# hdmi_fpc_rev2.net
KiCad netlist of a schematic drawn in EAGLE
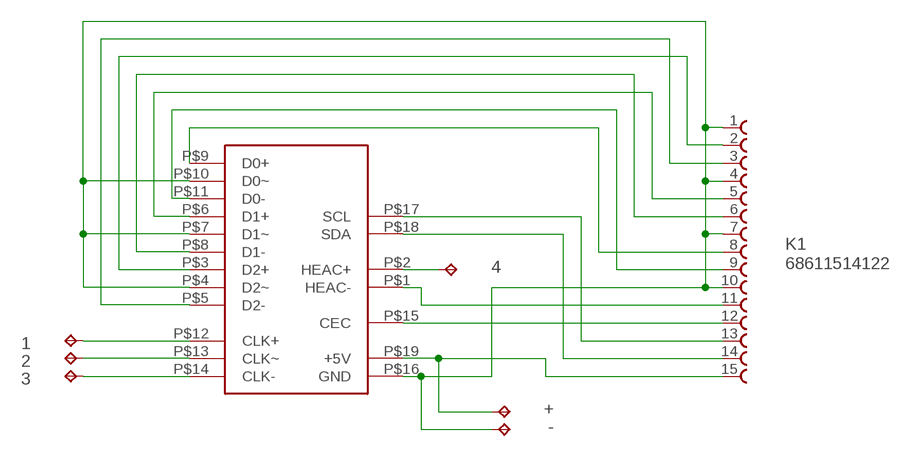
[diagram p0: schematic, sheet 1]

(export (version "E")
  (design (tool "Eeschema 10.0.6"))
  (components
    (comp (ref "+")
      (value "TPPAD1-13")
      (footprint "eagle-import:P1-13")
      (libsource (lib "eagle-import") (part "TPPAD1-13"))
    )
    (comp (ref "-")
      (value "TPPAD1-13")
      (footprint "eagle-import:P1-13")
      (libsource (lib "eagle-import") (part "TPPAD1-13"))
    )
    (comp (ref "1")
      (value "TPPAD1-13")
      (footprint "eagle-import:P1-13")
      (libsource (lib "eagle-import") (part "TPPAD1-13"))
    )
    (comp (ref "2")
      (value "TPPAD1-13")
      (footprint "eagle-import:P1-13")
      (libsource (lib "eagle-import") (part "TPPAD1-13"))
    )
    (comp (ref "3")
      (value "TPPAD1-13")
      (footprint "eagle-import:P1-13")
      (libsource (lib "eagle-import") (part "TPPAD1-13"))
    )
    (comp (ref "4")
      (value "TPPAD1-13")
      (footprint "eagle-import:P1-13")
      (libsource (lib "eagle-import") (part "TPPAD1-13"))
    )
    (comp (ref "K1")
      (value "68611514122")
      (footprint "eagle-import:68611514122")
      (libsource (lib "eagle-import") (part "68611514122"))
    )
    (comp (ref "U$1")
      (value "HDMI_MICRO")
      (footprint "eagle-import:MICRO_HDMI")
      (libsource (lib "eagle-import") (part "HDMI_MICRO"))
    )
  )
  (nets
    (net (code "1") (name "Net-(U$1-+5V)") (class "Default")
      (node (ref "+") (pin "TP") (pinfunction "TP_TP") (pintype "input"))
      (node (ref "K1") (pin "15") (pinfunction "15_15") (pintype "passive"))
      (node (ref "U$1") (pin "P$19") (pinfunction "+5V_P$19") (pintype "bidirectional"))
    )
    (net (code "2") (name "Net-(U$1-CEC)") (class "Default")
      (node (ref "K1") (pin "12") (pinfunction "12_12") (pintype "passive"))
      (node (ref "U$1") (pin "P$15") (pinfunction "CEC_P$15") (pintype "bidirectional"))
    )
    (net (code "3") (name "Net-(U$1-CLK+)") (class "Default")
      (node (ref "1") (pin "TP") (pinfunction "TP_TP") (pintype "input"))
      (node (ref "U$1") (pin "P$12") (pinfunction "CLK+_P$12") (pintype "bidirectional"))
    )
    (net (code "4") (name "Net-(U$1-CLK-)") (class "Default")
      (node (ref "3") (pin "TP") (pinfunction "TP_TP") (pintype "input"))
      (node (ref "U$1") (pin "P$14") (pinfunction "CLK-_P$14") (pintype "bidirectional"))
    )
    (net (code "5") (name "Net-(U$1-CLK~{})") (class "Default")
      (node (ref "2") (pin "TP") (pinfunction "TP_TP") (pintype "input"))
      (node (ref "U$1") (pin "P$13") (pinfunction "CLK~{}_P$13") (pintype "bidirectional"))
    )
    (net (code "6") (name "Net-(U$1-D0+)") (class "Default")
      (node (ref "K1") (pin "8") (pinfunction "8_8") (pintype "passive"))
      (node (ref "U$1") (pin "P$9") (pinfunction "D0+_P$9") (pintype "bidirectional"))
    )
    (net (code "7") (name "Net-(U$1-D0-)") (class "Default")
      (node (ref "K1") (pin "9") (pinfunction "9_9") (pintype "passive"))
      (node (ref "U$1") (pin "P$11") (pinfunction "D0-_P$11") (pintype "bidirectional"))
    )
    (net (code "8") (name "Net-(U$1-D0~{})") (class "Default")
      (node (ref "-") (pin "TP") (pinfunction "TP_TP") (pintype "input"))
      (node (ref "K1") (pin "1") (pinfunction "1_1") (pintype "passive"))
      (node (ref "K1") (pin "10") (pinfunction "10_10") (pintype "passive"))
      (node (ref "K1") (pin "4") (pinfunction "4_4") (pintype "passive"))
      (node (ref "K1") (pin "7") (pinfunction "7_7") (pintype "passive"))
      (node (ref "U$1") (pin "P$10") (pinfunction "D0~{}_P$10") (pintype "bidirectional"))
      (node (ref "U$1") (pin "P$16") (pinfunction "GND_P$16") (pintype "bidirectional"))
      (node (ref "U$1") (pin "P$4") (pinfunction "D2~{}_P$4") (pintype "bidirectional"))
      (node (ref "U$1") (pin "P$7") (pinfunction "D1~{}_P$7") (pintype "bidirectional"))
    )
    (net (code "9") (name "Net-(U$1-D1+)") (class "Default")
      (node (ref "K1") (pin "5") (pinfunction "5_5") (pintype "passive"))
      (node (ref "U$1") (pin "P$6") (pinfunction "D1+_P$6") (pintype "bidirectional"))
    )
    (net (code "10") (name "Net-(U$1-D1-)") (class "Default")
      (node (ref "K1") (pin "6") (pinfunction "6_6") (pintype "passive"))
      (node (ref "U$1") (pin "P$8") (pinfunction "D1-_P$8") (pintype "bidirectional"))
    )
    (net (code "11") (name "Net-(U$1-D2+)") (class "Default")
      (node (ref "K1") (pin "2") (pinfunction "2_2") (pintype "passive"))
      (node (ref "U$1") (pin "P$3") (pinfunction "D2+_P$3") (pintype "bidirectional"))
    )
    (net (code "12") (name "Net-(U$1-D2-)") (class "Default")
      (node (ref "K1") (pin "3") (pinfunction "3_3") (pintype "passive"))
      (node (ref "U$1") (pin "P$5") (pinfunction "D2-_P$5") (pintype "bidirectional"))
    )
    (net (code "13") (name "Net-(U$1-HEAC+)") (class "Default")
      (node (ref "4") (pin "TP") (pinfunction "TP_TP") (pintype "input"))
      (node (ref "U$1") (pin "P$2") (pinfunction "HEAC+_P$2") (pintype "bidirectional"))
    )
    (net (code "14") (name "Net-(U$1-HEAC-)") (class "Default")
      (node (ref "K1") (pin "11") (pinfunction "11_11") (pintype "passive"))
      (node (ref "U$1") (pin "P$1") (pinfunction "HEAC-_P$1") (pintype "bidirectional"))
    )
    (net (code "15") (name "Net-(U$1-SCL)") (class "Default")
      (node (ref "K1") (pin "13") (pinfunction "13_13") (pintype "passive"))
      (node (ref "U$1") (pin "P$17") (pinfunction "SCL_P$17") (pintype "bidirectional"))
    )
    (net (code "16") (name "Net-(U$1-SDA)") (class "Default")
      (node (ref "K1") (pin "14") (pinfunction "14_14") (pintype "passive"))
      (node (ref "U$1") (pin "P$18") (pinfunction "SDA_P$18") (pintype "bidirectional"))
    )
  )
)
